# ECBoard_v3.net
KiCad netlist of a schematic drawn in EAGLE
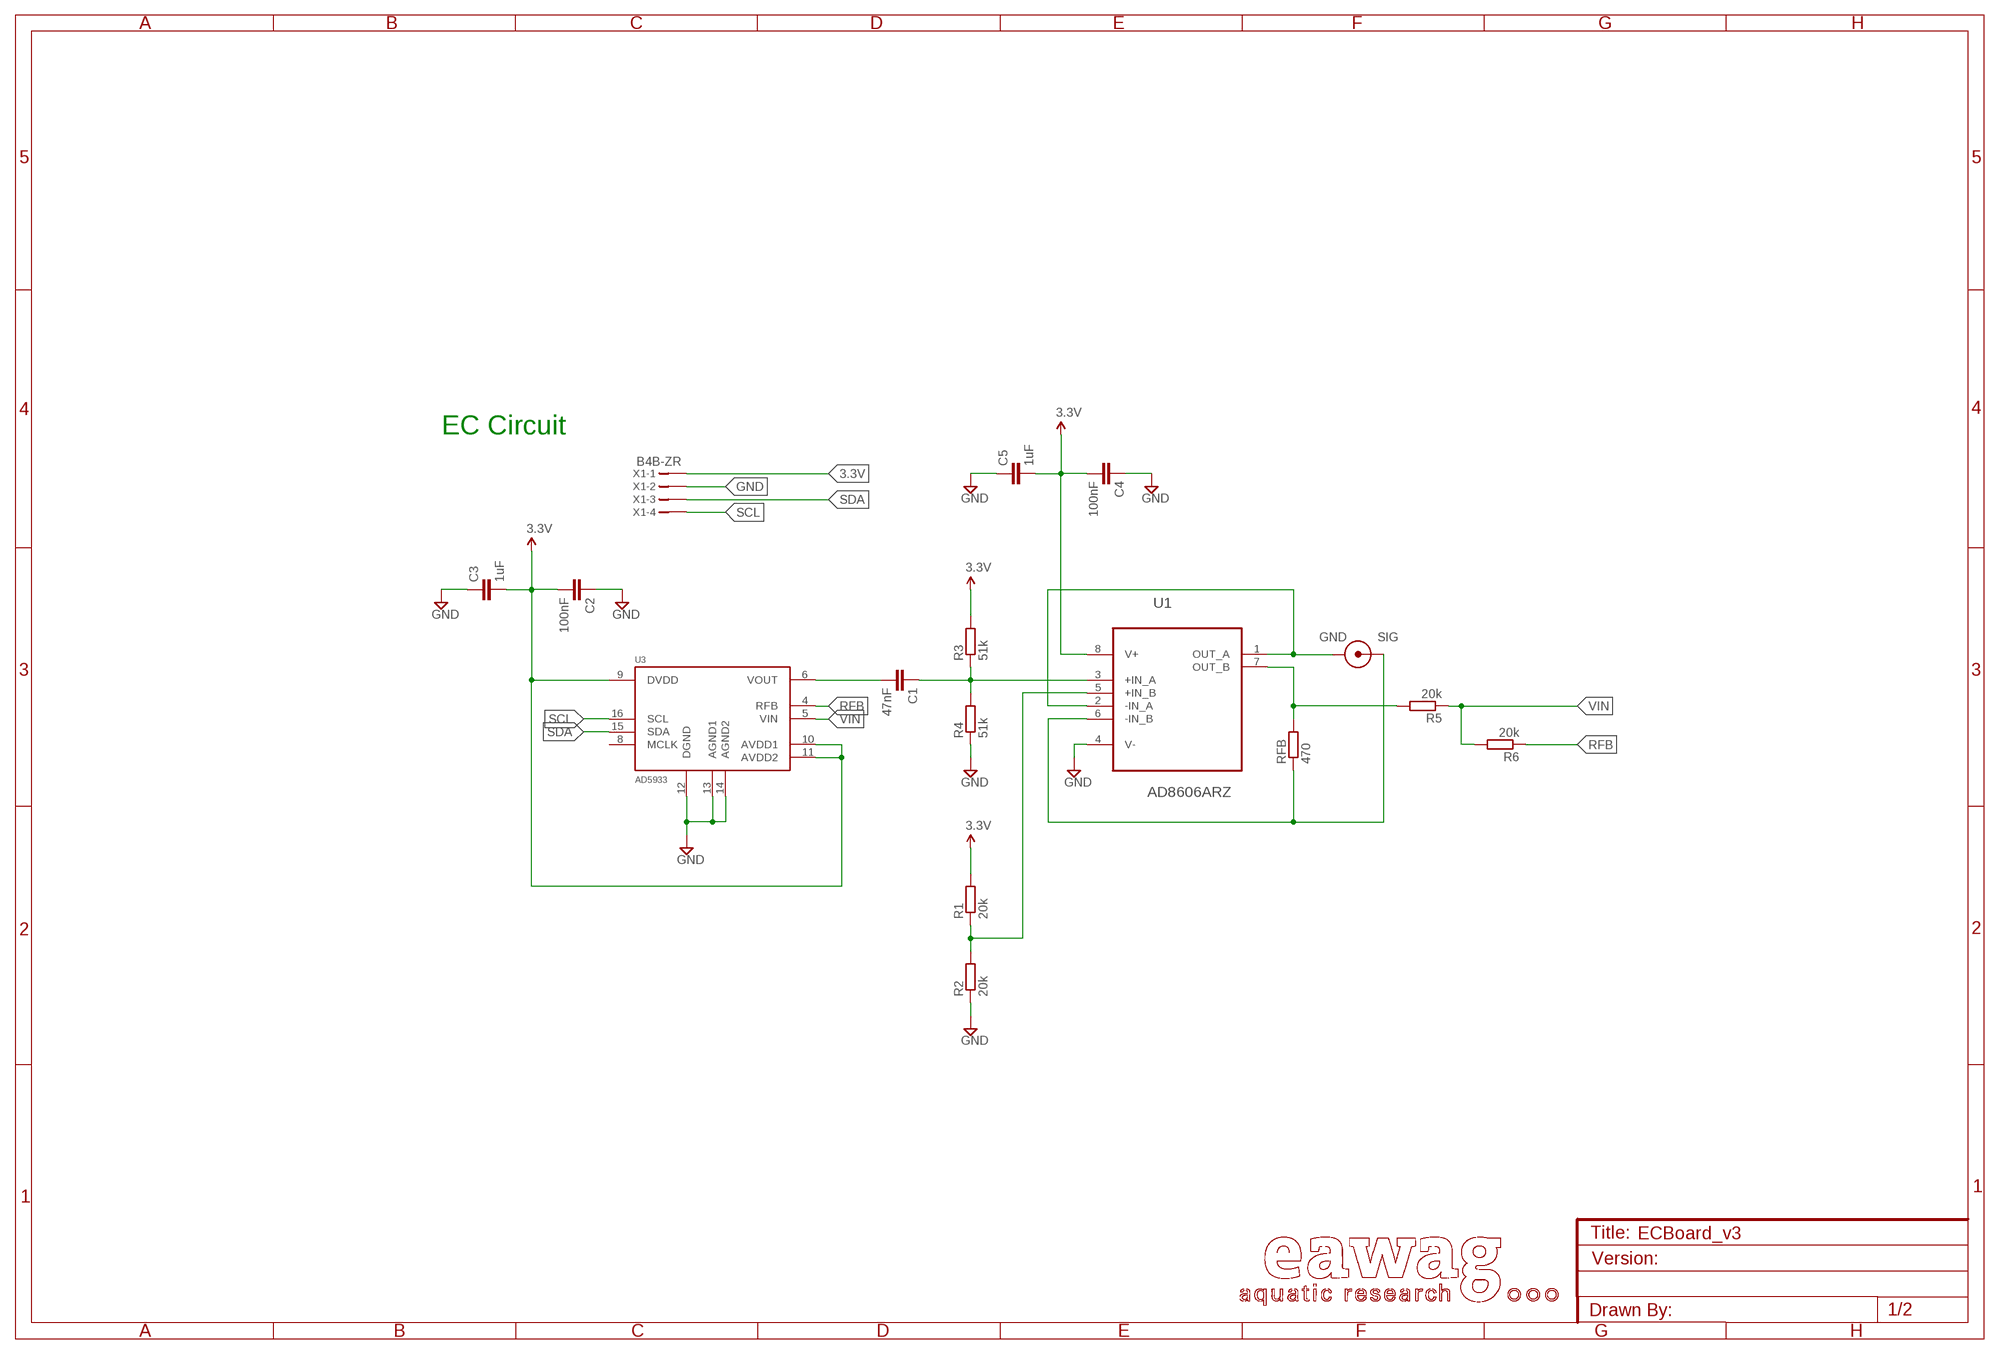
[diagram p0: schematic, sheet 1]
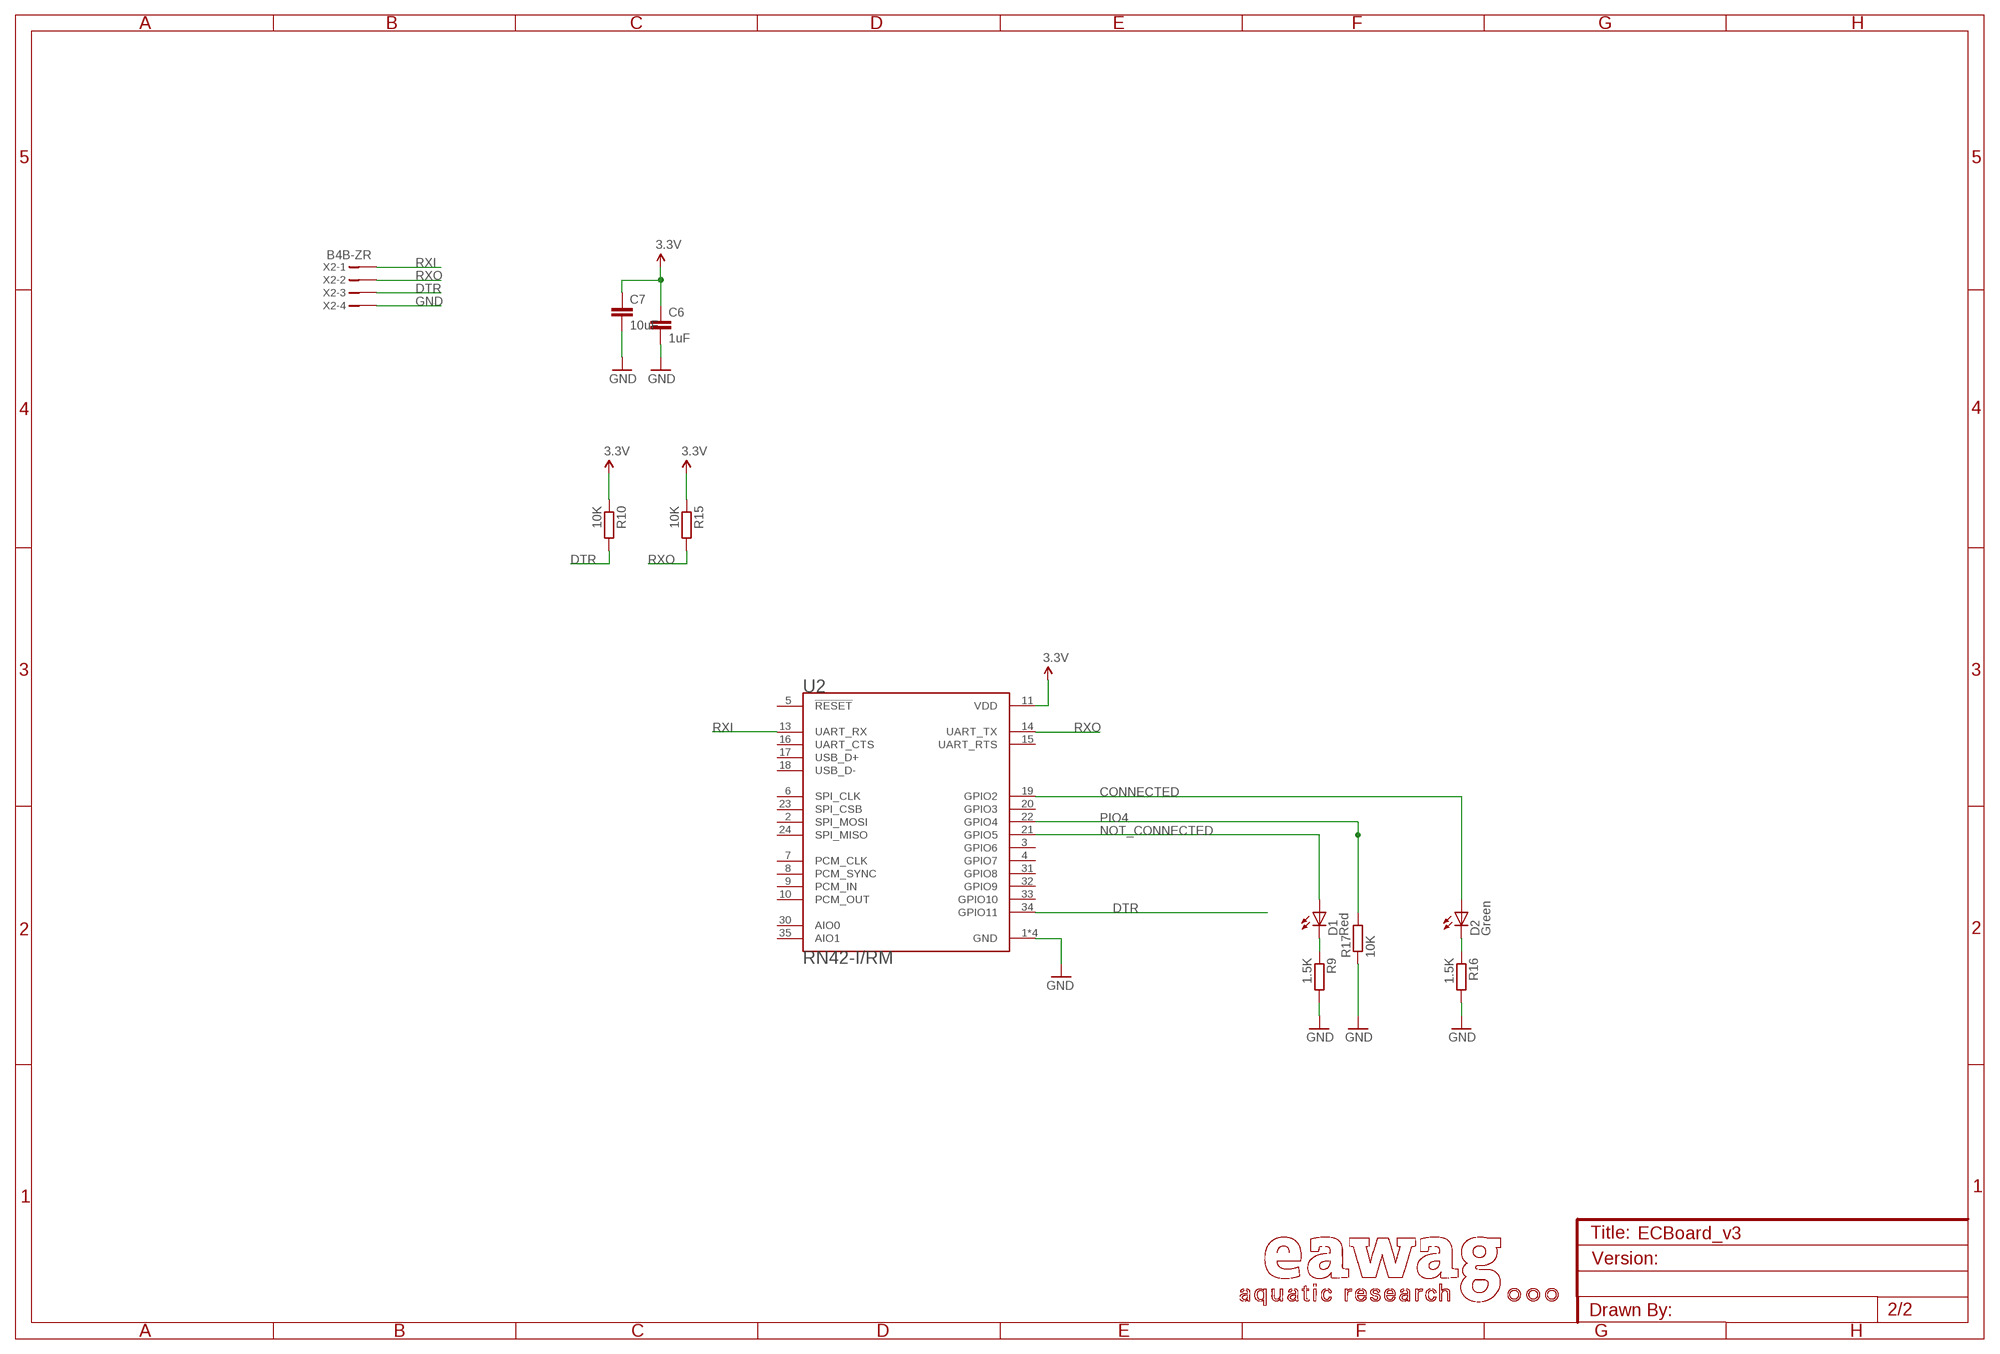
[diagram p1: schematic, sheet 2]

(export (version "E")
  (design (tool "Eeschema 10.0.6"))
  (components
    (comp (ref "C1")
      (value "47nF")
      (footprint "eagle-import:C0805")
      (libsource (lib "eagle-import") (part "rcl_C-EUC0805"))
    )
    (comp (ref "C2")
      (value "100nF")
      (footprint "eagle-import:C0805")
      (libsource (lib "eagle-import") (part "rcl_C-EUC0805"))
    )
    (comp (ref "C3")
      (value "1uF")
      (footprint "eagle-import:C0805")
      (libsource (lib "eagle-import") (part "C-EUC0805"))
    )
    (comp (ref "C4")
      (value "100nF")
      (footprint "eagle-import:C0805")
      (libsource (lib "eagle-import") (part "rcl_C-EUC0805"))
    )
    (comp (ref "C5")
      (value "1uF")
      (footprint "eagle-import:C0805")
      (libsource (lib "eagle-import") (part "C-EUC0805"))
    )
    (comp (ref "R1")
      (value "20k")
      (footprint "eagle-import:R0805")
      (libsource (lib "eagle-import") (part "rcl_R-EU_R0805"))
    )
    (comp (ref "R2")
      (value "20k")
      (footprint "eagle-import:R0805")
      (libsource (lib "eagle-import") (part "rcl_R-EU_R0805"))
    )
    (comp (ref "R3")
      (value "51k")
      (footprint "eagle-import:R0805")
      (libsource (lib "eagle-import") (part "rcl_R-EU_R0805"))
    )
    (comp (ref "R4")
      (value "51k")
      (footprint "eagle-import:R0805")
      (libsource (lib "eagle-import") (part "rcl_R-EU_R0805"))
    )
    (comp (ref "R5")
      (value "20k")
      (footprint "eagle-import:R0805")
      (libsource (lib "eagle-import") (part "rcl_R-EU_R0805"))
    )
    (comp (ref "R6")
      (value "20k")
      (footprint "eagle-import:R0805")
      (libsource (lib "eagle-import") (part "rcl_R-EU_R0805"))
    )
    (comp (ref "RFB")
      (value "470")
      (footprint "eagle-import:R0805")
      (libsource (lib "eagle-import") (part "rcl_R-EU_R0805"))
    )
    (comp (ref "U$1")
      (value "CON_HANNA")
      (footprint "eagle-import:CON_HANNA")
      (libsource (lib "eagle-import") (part "CON_HANNA"))
    )
    (comp (ref "U1")
      (value "AD8606ARZ")
      (footprint "eagle-import:SOIC127P600X175-8N")
      (libsource (lib "eagle-import") (part "AD8606ARZ"))
    )
    (comp (ref "U3")
      (value "AD5933")
      (footprint "eagle-import:SSOP16")
      (libsource (lib "eagle-import") (part "AD5933"))
    )
    (comp (ref "X1")
      (value "B4B-ZR")
      (footprint "eagle-import:B4B-ZR")
      (fields (field (name "MF") "FARNELL") (field (name "MPN") "B4B-ZR(LF)(SN)"))
      (libsource (lib "eagle-import") (part "?4B-ZRB"))
    )
    (comp (ref "C6")
      (value "1uF")
      (footprint "eagle-import:C0805")
      (libsource (lib "eagle-import") (part "C-EUC0805"))
    )
    (comp (ref "C7")
      (value "10uF")
      (footprint "eagle-import:C0805")
      (libsource (lib "eagle-import") (part "C-EUC0805"))
    )
    (comp (ref "D1")
      (value "Red")
      (footprint "eagle-import:LED-0603")
      (libsource (lib "eagle-import") (part "LED0603"))
    )
    (comp (ref "D2")
      (value "Green")
      (footprint "eagle-import:LED-0603")
      (libsource (lib "eagle-import") (part "LED0603"))
    )
    (comp (ref "R9")
      (value "1.5K")
      (footprint "eagle-import:R0805")
      (libsource (lib "eagle-import") (part "R-EU_R0805"))
    )
    (comp (ref "R10")
      (value "10K")
      (footprint "eagle-import:R0805")
      (libsource (lib "eagle-import") (part "R-EU_R0805"))
    )
    (comp (ref "R15")
      (value "10K")
      (footprint "eagle-import:R0805")
      (libsource (lib "eagle-import") (part "R-EU_R0805"))
    )
    (comp (ref "R16")
      (value "1.5K")
      (footprint "eagle-import:R0805")
      (libsource (lib "eagle-import") (part "R-EU_R0805"))
    )
    (comp (ref "R17")
      (value "10K")
      (footprint "eagle-import:R0805")
      (libsource (lib "eagle-import") (part "R-EU_R0805"))
    )
    (comp (ref "U2")
      (value "RN42-I/RM")
      (footprint "eagle-import:XCVR_RN42-I_RM")
      (fields (field (name "MF") "Microchip"))
      (libsource (lib "eagle-import") (part "RN42-I/RM"))
    )
    (comp (ref "X2")
      (value "B4B-ZR")
      (footprint "eagle-import:B4B-ZR")
      (fields (field (name "MF") "FARNELL") (field (name "MPN") "B4B-ZR(LF)(SN)"))
      (libsource (lib "eagle-import") (part "?4B-ZRB"))
    )
  )
  (nets
    (net (code "1") (name "3.3V") (class "Default")
      (node (ref "C2") (pin "2") (pinfunction "2_2") (pintype "passive"))
      (node (ref "C3") (pin "2") (pinfunction "2_2") (pintype "passive"))
      (node (ref "C4") (pin "2") (pinfunction "2_2") (pintype "passive"))
      (node (ref "C5") (pin "2") (pinfunction "2_2") (pintype "passive"))
      (node (ref "C6") (pin "1") (pinfunction "1_1") (pintype "passive"))
      (node (ref "C7") (pin "1") (pinfunction "1_1") (pintype "passive"))
      (node (ref "R1") (pin "2") (pinfunction "2_2") (pintype "passive"))
      (node (ref "R10") (pin "1") (pinfunction "1_1") (pintype "passive"))
      (node (ref "R15") (pin "1") (pinfunction "1_1") (pintype "passive"))
      (node (ref "R3") (pin "2") (pinfunction "2_2") (pintype "passive"))
      (node (ref "U1") (pin "8") (pinfunction "V+_8") (pintype "power_in"))
      (node (ref "U2") (pin "11") (pinfunction "VDD_11") (pintype "power_in"))
      (node (ref "U3") (pin "10") (pinfunction "AVDD1_10") (pintype "bidirectional"))
      (node (ref "U3") (pin "11") (pinfunction "AVDD2_11") (pintype "bidirectional"))
      (node (ref "U3") (pin "9") (pinfunction "DVDD_9") (pintype "bidirectional"))
      (node (ref "X1") (pin "1") (pinfunction "1_1") (pintype "passive"))
    )
    (net (code "2") (name "CONNECTED") (class "Default")
      (node (ref "D2") (pin "A") (pinfunction "A_A") (pintype "passive"))
      (node (ref "U2") (pin "19") (pinfunction "GPIO2_19") (pintype "bidirectional"))
    )
    (net (code "3") (name "DTR") (class "Default")
      (node (ref "R10") (pin "2") (pinfunction "2_2") (pintype "passive"))
      (node (ref "U2") (pin "34") (pinfunction "GPIO11_34") (pintype "bidirectional"))
      (node (ref "X2") (pin "3") (pinfunction "1_3") (pintype "passive"))
    )
    (net (code "4") (name "GND") (class "Default")
      (node (ref "C2") (pin "1") (pinfunction "1_1") (pintype "passive"))
      (node (ref "C3") (pin "1") (pinfunction "1_1") (pintype "passive"))
      (node (ref "C4") (pin "1") (pinfunction "1_1") (pintype "passive"))
      (node (ref "C5") (pin "1") (pinfunction "1_1") (pintype "passive"))
      (node (ref "C6") (pin "2") (pinfunction "2_2") (pintype "passive"))
      (node (ref "C7") (pin "2") (pinfunction "2_2") (pintype "passive"))
      (node (ref "R16") (pin "2") (pinfunction "2_2") (pintype "passive"))
      (node (ref "R17") (pin "1") (pinfunction "1_1") (pintype "passive"))
      (node (ref "R2") (pin "1") (pinfunction "1_1") (pintype "passive"))
      (node (ref "R4") (pin "1") (pinfunction "1_1") (pintype "passive"))
      (node (ref "R9") (pin "2") (pinfunction "2_2") (pintype "passive"))
      (node (ref "U1") (pin "4") (pinfunction "V-_4") (pintype "power_in"))
      (node (ref "U2") (pin "1") (pinfunction "GND_1") (pintype "power_in"))
      (node (ref "U2") (pin "12") (pinfunction "GND_12") (pintype "power_in"))
      (node (ref "U2") (pin "28") (pinfunction "GND_28") (pintype "power_in"))
      (node (ref "U2") (pin "29") (pinfunction "GND_29") (pintype "power_in"))
      (node (ref "U3") (pin "12") (pinfunction "DGND_12") (pintype "bidirectional"))
      (node (ref "U3") (pin "13") (pinfunction "AGND1_13") (pintype "bidirectional"))
      (node (ref "U3") (pin "14") (pinfunction "AGND2_14") (pintype "bidirectional"))
      (node (ref "X1") (pin "2") (pinfunction "1_2") (pintype "passive"))
      (node (ref "X2") (pin "4") (pinfunction "1_4") (pintype "passive"))
    )
    (net (code "5") (name "NOT_CONNECTED") (class "Default")
      (node (ref "D1") (pin "A") (pinfunction "A_A") (pintype "passive"))
      (node (ref "U2") (pin "21") (pinfunction "GPIO5_21") (pintype "bidirectional"))
    )
    (net (code "6") (name "Net-(D1-PadC)") (class "Default")
      (node (ref "D1") (pin "C") (pinfunction "C_C") (pintype "passive"))
      (node (ref "R9") (pin "1") (pinfunction "1_1") (pintype "passive"))
    )
    (net (code "7") (name "Net-(D2-PadC)") (class "Default")
      (node (ref "D2") (pin "C") (pinfunction "C_C") (pintype "passive"))
      (node (ref "R16") (pin "1") (pinfunction "1_1") (pintype "passive"))
    )
    (net (code "8") (name "Net-(U1-+IN_A)") (class "Default")
      (node (ref "C1") (pin "1") (pinfunction "1_1") (pintype "passive"))
      (node (ref "R3") (pin "1") (pinfunction "1_1") (pintype "passive"))
      (node (ref "R4") (pin "2") (pinfunction "2_2") (pintype "passive"))
      (node (ref "U1") (pin "3") (pinfunction "+IN_A_3") (pintype "input"))
    )
    (net (code "9") (name "Net-(U1-+IN_B)") (class "Default")
      (node (ref "R1") (pin "1") (pinfunction "1_1") (pintype "passive"))
      (node (ref "R2") (pin "2") (pinfunction "2_2") (pintype "passive"))
      (node (ref "U1") (pin "5") (pinfunction "+IN_B_5") (pintype "input"))
    )
    (net (code "10") (name "Net-(U1--IN_A)") (class "Default")
      (node (ref "U$1") (pin "CON_GND") (pinfunction "CON_GND_CON_GND") (pintype "bidirectional"))
      (node (ref "U1") (pin "1") (pinfunction "OUT_A_1") (pintype "output"))
      (node (ref "U1") (pin "2") (pinfunction "-IN_A_2") (pintype "input"))
    )
    (net (code "11") (name "Net-(U1--IN_B)") (class "Default")
      (node (ref "RFB") (pin "1") (pinfunction "1_1") (pintype "passive"))
      (node (ref "U$1") (pin "CON_SIG") (pinfunction "CON_SIG_CON_SIG") (pintype "bidirectional"))
      (node (ref "U1") (pin "6") (pinfunction "-IN_B_6") (pintype "input"))
    )
    (net (code "12") (name "Net-(U1-OUT_B)") (class "Default")
      (node (ref "R5") (pin "2") (pinfunction "2_2") (pintype "passive"))
      (node (ref "RFB") (pin "2") (pinfunction "2_2") (pintype "passive"))
      (node (ref "U1") (pin "7") (pinfunction "OUT_B_7") (pintype "output"))
    )
    (net (code "13") (name "Net-(U3-VOUT)") (class "Default")
      (node (ref "C1") (pin "2") (pinfunction "2_2") (pintype "passive"))
      (node (ref "U3") (pin "6") (pinfunction "VOUT_6") (pintype "bidirectional"))
    )
    (net (code "14") (name "PIO4") (class "Default")
      (node (ref "R17") (pin "2") (pinfunction "2_2") (pintype "passive"))
      (node (ref "U2") (pin "22") (pinfunction "GPIO4_22") (pintype "bidirectional"))
    )
    (net (code "15") (name "RFB") (class "Default")
      (node (ref "R6") (pin "1") (pinfunction "1_1") (pintype "passive"))
      (node (ref "U3") (pin "4") (pinfunction "RFB_4") (pintype "bidirectional"))
    )
    (net (code "16") (name "RXI") (class "Default")
      (node (ref "U2") (pin "13") (pinfunction "UART_RX_13") (pintype "input"))
      (node (ref "X2") (pin "1") (pinfunction "1_1") (pintype "passive"))
    )
    (net (code "17") (name "RXO") (class "Default")
      (node (ref "R15") (pin "2") (pinfunction "2_2") (pintype "passive"))
      (node (ref "U2") (pin "14") (pinfunction "UART_TX_14") (pintype "output"))
      (node (ref "X2") (pin "2") (pinfunction "1_2") (pintype "passive"))
    )
    (net (code "18") (name "SCL") (class "Default")
      (node (ref "U3") (pin "16") (pinfunction "SCL_16") (pintype "bidirectional"))
      (node (ref "X1") (pin "4") (pinfunction "1_4") (pintype "passive"))
    )
    (net (code "19") (name "SDA") (class "Default")
      (node (ref "U3") (pin "15") (pinfunction "SDA_15") (pintype "bidirectional"))
      (node (ref "X1") (pin "3") (pinfunction "1_3") (pintype "passive"))
    )
    (net (code "20") (name "VIN") (class "Default")
      (node (ref "R5") (pin "1") (pinfunction "1_1") (pintype "passive"))
      (node (ref "R6") (pin "2") (pinfunction "2_2") (pintype "passive"))
      (node (ref "U3") (pin "5") (pinfunction "VIN_5") (pintype "bidirectional"))
    )
    (net (code "21") (name "unconnected-(U2-AIO0-Pad30)") (class "Default")
      (node (ref "U2") (pin "30") (pinfunction "AIO0_30") (pintype "bidirectional"))
    )
    (net (code "22") (name "unconnected-(U2-AIO1-Pad35)") (class "Default")
      (node (ref "U2") (pin "35") (pinfunction "AIO1_35") (pintype "bidirectional"))
    )
    (net (code "23") (name "unconnected-(U2-GPIO3-Pad20)") (class "Default")
      (node (ref "U2") (pin "20") (pinfunction "GPIO3_20") (pintype "bidirectional"))
    )
    (net (code "24") (name "unconnected-(U2-GPIO6-Pad3)") (class "Default")
      (node (ref "U2") (pin "3") (pinfunction "GPIO6_3") (pintype "bidirectional"))
    )
    (net (code "25") (name "unconnected-(U2-GPIO7-Pad4)") (class "Default")
      (node (ref "U2") (pin "4") (pinfunction "GPIO7_4") (pintype "bidirectional"))
    )
    (net (code "26") (name "unconnected-(U2-GPIO8-Pad31)") (class "Default")
      (node (ref "U2") (pin "31") (pinfunction "GPIO8_31") (pintype "bidirectional"))
    )
    (net (code "27") (name "unconnected-(U2-GPIO9-Pad32)") (class "Default")
      (node (ref "U2") (pin "32") (pinfunction "GPIO9_32") (pintype "bidirectional"))
    )
    (net (code "28") (name "unconnected-(U2-GPIO10-Pad33)") (class "Default")
      (node (ref "U2") (pin "33") (pinfunction "GPIO10_33") (pintype "bidirectional"))
    )
    (net (code "29") (name "unconnected-(U2-PCM_CLK-Pad7)") (class "Default")
      (node (ref "U2") (pin "7") (pinfunction "PCM_CLK_7") (pintype "bidirectional"))
    )
    (net (code "30") (name "unconnected-(U2-PCM_IN-Pad9)") (class "Default")
      (node (ref "U2") (pin "9") (pinfunction "PCM_IN_9") (pintype "input"))
    )
    (net (code "31") (name "unconnected-(U2-PCM_OUT-Pad10)") (class "Default")
      (node (ref "U2") (pin "10") (pinfunction "PCM_OUT_10") (pintype "output"))
    )
    (net (code "32") (name "unconnected-(U2-PCM_SYNC-Pad8)") (class "Default")
      (node (ref "U2") (pin "8") (pinfunction "PCM_SYNC_8") (pintype "bidirectional"))
    )
    (net (code "33") (name "unconnected-(U2-SPI_CLK-Pad6)") (class "Default")
      (node (ref "U2") (pin "6") (pinfunction "SPI_CLK_6") (pintype "input"))
    )
    (net (code "34") (name "unconnected-(U2-SPI_CSB-Pad23)") (class "Default")
      (node (ref "U2") (pin "23") (pinfunction "SPI_CSB_23") (pintype "input"))
    )
    (net (code "35") (name "unconnected-(U2-SPI_MISO-Pad24)") (class "Default")
      (node (ref "U2") (pin "24") (pinfunction "SPI_MISO_24") (pintype "output"))
    )
    (net (code "36") (name "unconnected-(U2-SPI_MOSI-Pad2)") (class "Default")
      (node (ref "U2") (pin "2") (pinfunction "SPI_MOSI_2") (pintype "input"))
    )
    (net (code "37") (name "unconnected-(U2-UART_CTS-Pad16)") (class "Default")
      (node (ref "U2") (pin "16") (pinfunction "UART_CTS_16") (pintype "input"))
    )
    (net (code "38") (name "unconnected-(U2-UART_RTS-Pad15)") (class "Default")
      (node (ref "U2") (pin "15") (pinfunction "UART_RTS_15") (pintype "output"))
    )
    (net (code "39") (name "unconnected-(U2-USB_D+-Pad17)") (class "Default")
      (node (ref "U2") (pin "17") (pinfunction "USB_D+_17") (pintype "bidirectional"))
    )
    (net (code "40") (name "unconnected-(U2-USB_D--Pad18)") (class "Default")
      (node (ref "U2") (pin "18") (pinfunction "USB_D-_18") (pintype "bidirectional"))
    )
    (net (code "41") (name "unconnected-(U2-~{RESET}-Pad5)") (class "Default")
      (node (ref "U2") (pin "5") (pinfunction "~{RESET}_5") (pintype "input"))
    )
    (net (code "42") (name "unconnected-(U3-MCLK-Pad8)") (class "Default")
      (node (ref "U3") (pin "8") (pinfunction "MCLK_8") (pintype "bidirectional"))
    )
  )
)
